# OpenBook_schematic.net
KiCad netlist of a schematic drawn in EAGLE
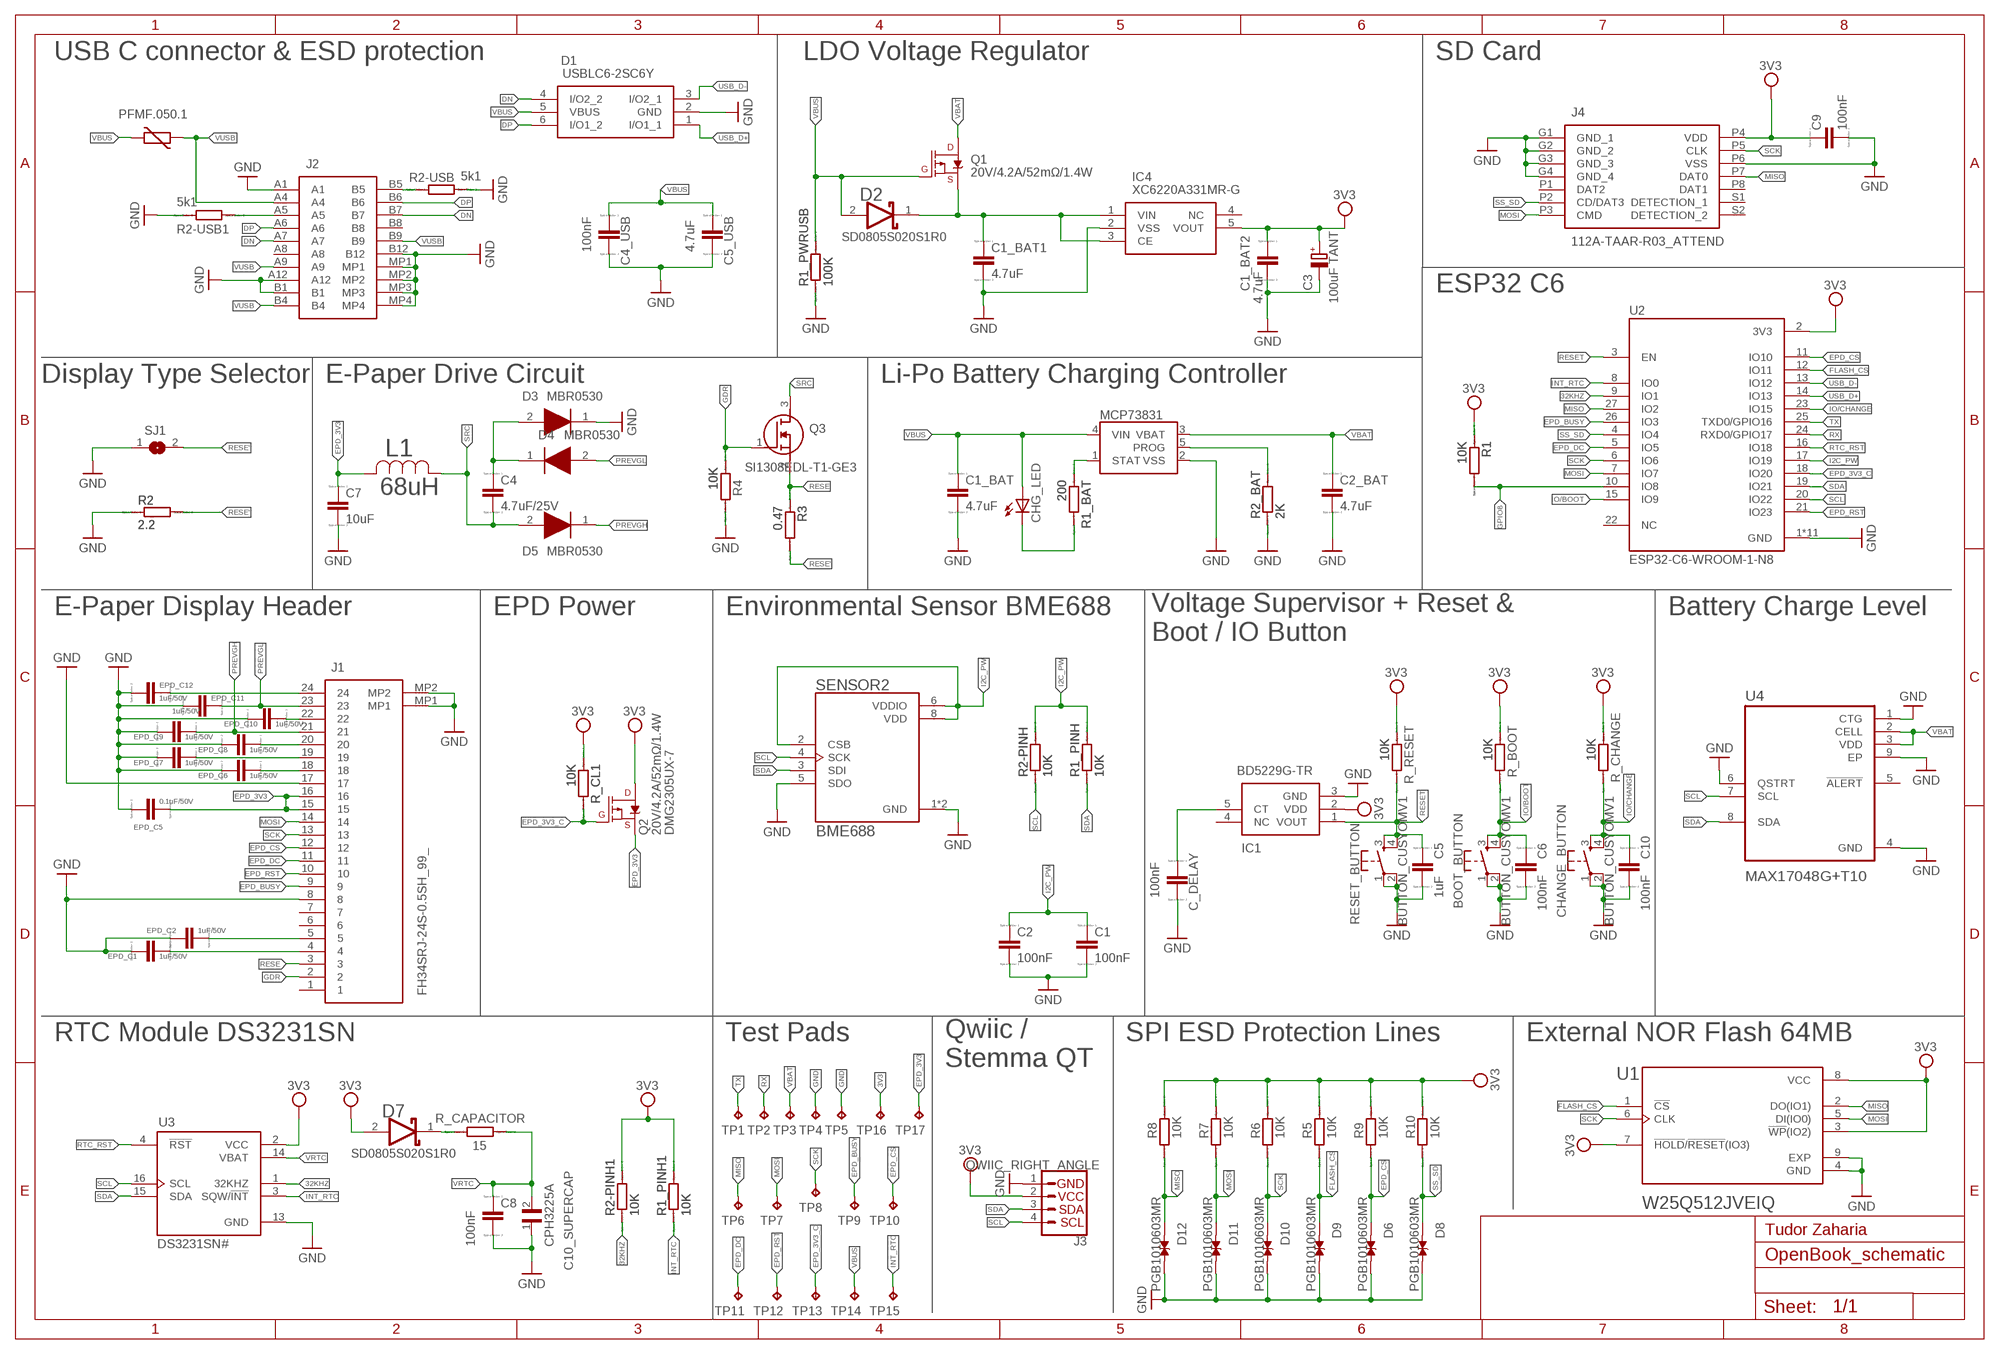
[diagram p0: schematic, sheet 1]

(export (version "E")
  (design (tool "Eeschema 10.0.6"))
  (components
    (comp (ref "BOOT_BUTTON")
      (value "BUTTON_CUSYOMV1")
      (footprint "eagle-import:MYBUTTON")
      (libsource (lib "eagle-import") (part "BUTTON_CUSYOMV1"))
    )
    (comp (ref "C1")
      (value "100nF")
      (footprint "eagle-import:EAGLE-LTSPICE_C0402")
      (libsource (lib "eagle-import") (part "EAGLE-LTSPICE_CC0402"))
    )
    (comp (ref "C1_BAT")
      (value "4.7uF")
      (footprint "eagle-import:EAGLE-LTSPICE_C0402")
      (libsource (lib "eagle-import") (part "EAGLE-LTSPICE_CC0402"))
    )
    (comp (ref "C1_BAT1")
      (value "4.7uF")
      (footprint "eagle-import:EAGLE-LTSPICE_C0402")
      (libsource (lib "eagle-import") (part "EAGLE-LTSPICE_CC0402"))
    )
    (comp (ref "C1_BAT2")
      (value "4.7uF")
      (footprint "eagle-import:EAGLE-LTSPICE_C0402")
      (libsource (lib "eagle-import") (part "EAGLE-LTSPICE_CC0402"))
    )
    (comp (ref "C2")
      (value "100nF")
      (footprint "eagle-import:EAGLE-LTSPICE_C0402")
      (libsource (lib "eagle-import") (part "EAGLE-LTSPICE_CC0402"))
    )
    (comp (ref "C2_BAT")
      (value "4.7uF")
      (footprint "eagle-import:EAGLE-LTSPICE_C0402")
      (libsource (lib "eagle-import") (part "EAGLE-LTSPICE_CC0402"))
    )
    (comp (ref "C3")
      (value "100uF TANT")
      (footprint "eagle-import:RCL_CT3528")
      (libsource (lib "eagle-import") (part "RCL_CPOL-EUCT3528"))
    )
    (comp (ref "C4")
      (value "4.7uF/25V")
      (footprint "eagle-import:EAGLE-LTSPICE_C0402")
      (libsource (lib "eagle-import") (part "EAGLE-LTSPICE_CC0402"))
    )
    (comp (ref "C4_USB")
      (value "100nF")
      (footprint "eagle-import:EAGLE-LTSPICE_C0402")
      (libsource (lib "eagle-import") (part "EAGLE-LTSPICE_CC0402"))
    )
    (comp (ref "C5")
      (value "1uF")
      (footprint "eagle-import:EAGLE-LTSPICE_C0402")
      (libsource (lib "eagle-import") (part "EAGLE-LTSPICE_CC0402"))
    )
    (comp (ref "C5_USB")
      (value "4.7uF")
      (footprint "eagle-import:EAGLE-LTSPICE_C0402")
      (libsource (lib "eagle-import") (part "EAGLE-LTSPICE_CC0402"))
    )
    (comp (ref "C6")
      (value "100nF")
      (footprint "eagle-import:EAGLE-LTSPICE_C0402")
      (libsource (lib "eagle-import") (part "EAGLE-LTSPICE_CC0402"))
    )
    (comp (ref "C7")
      (value "10uF")
      (footprint "eagle-import:EAGLE-LTSPICE_C0402")
      (libsource (lib "eagle-import") (part "EAGLE-LTSPICE_CC0402"))
    )
    (comp (ref "C8")
      (value "100nF")
      (footprint "eagle-import:EAGLE-LTSPICE_C0402")
      (libsource (lib "eagle-import") (part "EAGLE-LTSPICE_CC0402"))
    )
    (comp (ref "C9")
      (value "100nF")
      (footprint "eagle-import:EAGLE-LTSPICE_C0402")
      (libsource (lib "eagle-import") (part "EAGLE-LTSPICE_CC0402"))
    )
    (comp (ref "C10")
      (value "100nF")
      (footprint "eagle-import:EAGLE-LTSPICE_C0402")
      (libsource (lib "eagle-import") (part "EAGLE-LTSPICE_CC0402"))
    )
    (comp (ref "C10_SUPERCAP")
      (value "CPH3225A")
      (footprint "eagle-import:CAPCP3225X100N")
      (fields (field (name "MF") "Seiko Instruments"))
      (libsource (lib "eagle-import") (part "CPH3225A"))
    )
    (comp (ref "CHANGE_BUTTON")
      (value "BUTTON_CUSYOMV1")
      (footprint "eagle-import:MYBUTTON")
      (libsource (lib "eagle-import") (part "BUTTON_CUSYOMV1"))
    )
    (comp (ref "CHG_LED")
      (value "ADAFRUIT_LEDCHIP-LED0603")
      (footprint "eagle-import:ADAFRUIT_CHIP-LED0603")
      (libsource (lib "eagle-import") (part "ADAFRUIT_LEDCHIP-LED0603"))
    )
    (comp (ref "C_DELAY")
      (value "100nF")
      (footprint "eagle-import:EAGLE-LTSPICE_C0402")
      (libsource (lib "eagle-import") (part "EAGLE-LTSPICE_CC0402"))
    )
    (comp (ref "D1")
      (value "USBLC6-2SC6Y")
      (footprint "eagle-import:SOT95P280X145-6N")
      (fields (field (name "MF") "STMicroelectronics"))
      (libsource (lib "eagle-import") (part "USBLC6-2SC6Y"))
    )
    (comp (ref "D2")
      (value "ESP32_WROVER_AVX---SD0805S020S1R0_AVX_SD0805S020S1R0_0_0AVX_SD0805S020S1R0_0_0")
      (footprint "eagle-import:ESP32_WROVER_AVX---SD0805S020S1R0_AVX_SD0805S020S1R0_0")
      (fields
        (field (name "DIGIKEY_PART_NUMBER") "478-7800-1-ND")
        (field (name "MF") "AVX")
        (field (name "MOUSER_PART_NUMBER") "581-SD0805S020S1R0")
      )
      (libsource (lib "eagle-import") (part "ESP32_WROVER_AVX---SD0805S020S1R0_AVX_SD0805S020S1R0_0_0AVX_SD0805S020S1R0_0_0"))
    )
    (comp (ref "D3")
      (value "MBR0530")
      (footprint "eagle-import:SOD3716X135N")
      (fields (field (name "MF") "ON Semiconductor"))
      (libsource (lib "eagle-import") (part "MBR0530"))
    )
    (comp (ref "D4")
      (value "MBR0530")
      (footprint "eagle-import:SOD3716X135N")
      (fields (field (name "MF") "ON Semiconductor"))
      (libsource (lib "eagle-import") (part "MBR0530"))
    )
    (comp (ref "D5")
      (value "MBR0530")
      (footprint "eagle-import:SOD3716X135N")
      (fields (field (name "MF") "ON Semiconductor"))
      (libsource (lib "eagle-import") (part "MBR0530"))
    )
    (comp (ref "D6")
      (value "PGB1010603MR")
      (footprint "eagle-import:DIOC1608X36N")
      (fields (field (name "MF") "Littelfuse Inc."))
      (libsource (lib "eagle-import") (part "PGB1010603MR"))
    )
    (comp (ref "D7")
      (value "ESP32_WROVER_AVX---SD0805S020S1R0_AVX_SD0805S020S1R0_0_0AVX_SD0805S020S1R0_0_0")
      (footprint "eagle-import:ESP32_WROVER_AVX---SD0805S020S1R0_AVX_SD0805S020S1R0_0")
      (fields
        (field (name "DIGIKEY_PART_NUMBER") "478-7800-1-ND")
        (field (name "MF") "AVX")
        (field (name "MOUSER_PART_NUMBER") "581-SD0805S020S1R0")
      )
      (libsource (lib "eagle-import") (part "ESP32_WROVER_AVX---SD0805S020S1R0_AVX_SD0805S020S1R0_0_0AVX_SD0805S020S1R0_0_0"))
    )
    (comp (ref "D8")
      (value "PGB1010603MR")
      (footprint "eagle-import:DIOC1608X36N")
      (fields (field (name "MF") "Littelfuse Inc."))
      (libsource (lib "eagle-import") (part "PGB1010603MR"))
    )
    (comp (ref "D9")
      (value "PGB1010603MR")
      (footprint "eagle-import:DIOC1608X36N")
      (fields (field (name "MF") "Littelfuse Inc."))
      (libsource (lib "eagle-import") (part "PGB1010603MR"))
    )
    (comp (ref "D10")
      (value "PGB1010603MR")
      (footprint "eagle-import:DIOC1608X36N")
      (fields (field (name "MF") "Littelfuse Inc."))
      (libsource (lib "eagle-import") (part "PGB1010603MR"))
    )
    (comp (ref "D11")
      (value "PGB1010603MR")
      (footprint "eagle-import:DIOC1608X36N")
      (fields (field (name "MF") "Littelfuse Inc."))
      (libsource (lib "eagle-import") (part "PGB1010603MR"))
    )
    (comp (ref "D12")
      (value "PGB1010603MR")
      (footprint "eagle-import:DIOC1608X36N")
      (fields (field (name "MF") "Littelfuse Inc."))
      (libsource (lib "eagle-import") (part "PGB1010603MR"))
    )
    (comp (ref "EPD_C1")
      (value "1uF/50V")
      (footprint "eagle-import:EAGLE-LTSPICE_C0402")
      (libsource (lib "eagle-import") (part "EAGLE-LTSPICE_CC0402"))
    )
    (comp (ref "EPD_C2")
      (value "1uF/50V")
      (footprint "eagle-import:EAGLE-LTSPICE_C0402")
      (libsource (lib "eagle-import") (part "EAGLE-LTSPICE_CC0402"))
    )
    (comp (ref "EPD_C5")
      (value "0.1uF/50V")
      (footprint "eagle-import:EAGLE-LTSPICE_C0402")
      (libsource (lib "eagle-import") (part "EAGLE-LTSPICE_CC0402"))
    )
    (comp (ref "EPD_C6")
      (value "1uF/50V")
      (footprint "eagle-import:EAGLE-LTSPICE_C0402")
      (libsource (lib "eagle-import") (part "EAGLE-LTSPICE_CC0402"))
    )
    (comp (ref "EPD_C7")
      (value "1uF/50V")
      (footprint "eagle-import:EAGLE-LTSPICE_C0402")
      (libsource (lib "eagle-import") (part "EAGLE-LTSPICE_CC0402"))
    )
    (comp (ref "EPD_C8")
      (value "1uF/50V")
      (footprint "eagle-import:EAGLE-LTSPICE_C0402")
      (libsource (lib "eagle-import") (part "EAGLE-LTSPICE_CC0402"))
    )
    (comp (ref "EPD_C9")
      (value "1uF/50V")
      (footprint "eagle-import:EAGLE-LTSPICE_C0402")
      (libsource (lib "eagle-import") (part "EAGLE-LTSPICE_CC0402"))
    )
    (comp (ref "EPD_C10")
      (value "1uF/50V")
      (footprint "eagle-import:EAGLE-LTSPICE_C0402")
      (libsource (lib "eagle-import") (part "EAGLE-LTSPICE_CC0402"))
    )
    (comp (ref "EPD_C11")
      (value "1uF/50V")
      (footprint "eagle-import:EAGLE-LTSPICE_C0402")
      (libsource (lib "eagle-import") (part "EAGLE-LTSPICE_CC0402"))
    )
    (comp (ref "EPD_C12")
      (value "1uF/50V")
      (footprint "eagle-import:EAGLE-LTSPICE_C0402")
      (libsource (lib "eagle-import") (part "EAGLE-LTSPICE_CC0402"))
    )
    (comp (ref "IC1")
      (value "BD5229G-TR")
      (footprint "eagle-import:SOT95P280X125-5N")
      (fields (field (name "MOUSER_PART_NUMBER") "755-BD5229G-TR"))
      (libsource (lib "eagle-import") (part "BD5229G-TR"))
    )
    (comp (ref "IC4")
      (value "XC6220A331MR-G")
      (footprint "eagle-import:SOT95P280X120-5N")
      (fields (field (name "MOUSER_PART_NUMBER") "865-XC6220A331MR-G"))
      (libsource (lib "eagle-import") (part "XC6220A331MR-G"))
    )
    (comp (ref "J1")
      (value "FH34SRJ-24S-0.5SH_99_")
      (footprint "eagle-import:FH34SRJ24S05SH99")
      (fields
        (field (name "MANUFACTURER_PART_NUMBER") "FH34SRJ-24S-0.5SH(99)")
        (field (name "MOUSER_PART_NUMBER") "798-FH34SRJ24S05SH99")
      )
      (libsource (lib "eagle-import") (part "FH34SRJ-24S-0.5SH_99_"))
    )
    (comp (ref "J2")
      (value "SAMACSYS_PARTS_USB4110-GF-A")
      (footprint "eagle-import:SAMACSYS_PARTS_USB4110GFA")
      (fields
        (field (name "MANUFACTURER_PART_NUMBER") "USB4110-GF-A")
        (field (name "MOUSER_PART_NUMBER") "640-USB4110-GF-A")
      )
      (libsource (lib "eagle-import") (part "SAMACSYS_PARTS_USB4110-GF-A"))
    )
    (comp (ref "J3")
      (value "QWIIC_RIGHT_ANGLE")
      (footprint "eagle-import:JST04_1MM_RA")
      (libsource (lib "eagle-import") (part "QWIIC_CONNECTORJS-1MM"))
    )
    (comp (ref "J4")
      (value "112A-TAAR-R03_ATTEND")
      (footprint "eagle-import:112ATAARR03ATTEND")
      (fields (field (name "MANUFACTURER_PART_NUMBER") "112A-TAAR-R03 ATTEND"))
      (libsource (lib "eagle-import") (part "112A-TAAR-R03_ATTEND"))
    )
    (comp (ref "L1")
      (value "68uH")
      (footprint "eagle-import:IND_4828-WE-TPC_WRE")
      (fields
        (field (name "MANUFACTURER_PART_NUMBER") "744043680")
        (field (name "COPYRIGHT") "Copyright (C) 2024 Ultra Librarian. All rights reserved.")
      )
      (libsource (lib "eagle-import") (part "744043680IND_4828-WE-TPC_WRE"))
    )
    (comp (ref "MCP73831")
      (value "ESP32_WROVER_SPARKFUN-IC-POWER_MCP73831")
      (footprint "eagle-import:ESP32_WROVER_SPARKFUN-IC-POWER_SOT23-5")
      (libsource (lib "eagle-import") (part "ESP32_WROVER_SPARKFUN-IC-POWER_MCP73831"))
    )
    (comp (ref "PFMF.050.1")
      (value "ESP32C6_VARISTORCN1812")
      (footprint "eagle-import:ESP32C6_VARISTOR_CT_CN1812")
      (libsource (lib "eagle-import") (part "ESP32C6_VARISTORCN1812"))
    )
    (comp (ref "Q1")
      (value "20V/4.2A/52mΩ/1.4W")
      (footprint "eagle-import:ESP32_WROVER_SPARKFUN-DISCRETESEMI_SOT23-3")
      (libsource (lib "eagle-import") (part "ESP32_WROVER_SPARKFUN-DISCRETESEMI_MOSFET_PCH-DMG2305UX-7"))
    )
    (comp (ref "Q2")
      (value "20V/4.2A/52mΩ/1.4W")
      (footprint "eagle-import:ESP32_WROVER_SPARKFUN-DISCRETESEMI_SOT23-3")
      (libsource (lib "eagle-import") (part "ESP32_WROVER_SPARKFUN-DISCRETESEMI_MOSFET_PCH-DMG2305UX-7"))
    )
    (comp (ref "Q3")
      (value "SI1308EDL-T1-GE3")
      (footprint "eagle-import:SOT65P210X110-3N")
      (fields (field (name "MF") "Vishay Siliconix"))
      (libsource (lib "eagle-import") (part "SI1308EDL-T1-GE3"))
    )
    (comp (ref "R1")
      (value "10K")
      (footprint "eagle-import:ESP32_WROVER_EAGLE-LTSPICE_R0402")
      (libsource (lib "eagle-import") (part "ESP32_WROVER_EAGLE-LTSPICE_RR0402"))
    )
    (comp (ref "R1_BAT")
      (value "200")
      (footprint "eagle-import:ESP32_WROVER_EAGLE-LTSPICE_R0402")
      (libsource (lib "eagle-import") (part "ESP32_WROVER_EAGLE-LTSPICE_RR0402"))
    )
    (comp (ref "R1_PINH")
      (value "10K")
      (footprint "eagle-import:ESP32_WROVER_EAGLE-LTSPICE_R0402")
      (libsource (lib "eagle-import") (part "ESP32_WROVER_EAGLE-LTSPICE_RR0402"))
    )
    (comp (ref "R1_PINH1")
      (value "10K")
      (footprint "eagle-import:ESP32_WROVER_EAGLE-LTSPICE_R0402")
      (libsource (lib "eagle-import") (part "ESP32_WROVER_EAGLE-LTSPICE_RR0402"))
    )
    (comp (ref "R1_PWRUSB")
      (value "100K")
      (footprint "eagle-import:ESP32_WROVER_EAGLE-LTSPICE_R0402")
      (libsource (lib "eagle-import") (part "ESP32_WROVER_EAGLE-LTSPICE_RR0402"))
    )
    (comp (ref "R2")
      (value "2.2")
      (footprint "eagle-import:ESP32_WROVER_EAGLE-LTSPICE_R0402")
      (libsource (lib "eagle-import") (part "ESP32_WROVER_EAGLE-LTSPICE_RR0402"))
    )
    (comp (ref "R2-PINH")
      (value "10K")
      (footprint "eagle-import:ESP32_WROVER_EAGLE-LTSPICE_R0402")
      (libsource (lib "eagle-import") (part "ESP32_WROVER_EAGLE-LTSPICE_RR0402"))
    )
    (comp (ref "R2-PINH1")
      (value "10K")
      (footprint "eagle-import:ESP32_WROVER_EAGLE-LTSPICE_R0402")
      (libsource (lib "eagle-import") (part "ESP32_WROVER_EAGLE-LTSPICE_RR0402"))
    )
    (comp (ref "R2-USB")
      (value "5k1")
      (footprint "eagle-import:ESP32_WROVER_EAGLE-LTSPICE_R0402")
      (libsource (lib "eagle-import") (part "ESP32_WROVER_EAGLE-LTSPICE_RR0402"))
    )
    (comp (ref "R2-USB1")
      (value "5k1")
      (footprint "eagle-import:ESP32_WROVER_EAGLE-LTSPICE_R0402")
      (libsource (lib "eagle-import") (part "ESP32_WROVER_EAGLE-LTSPICE_RR0402"))
    )
    (comp (ref "R2_BAT")
      (value "2K")
      (footprint "eagle-import:ESP32_WROVER_EAGLE-LTSPICE_R0402")
      (libsource (lib "eagle-import") (part "ESP32_WROVER_EAGLE-LTSPICE_RR0402"))
    )
    (comp (ref "R3")
      (value "0.47")
      (footprint "eagle-import:ESP32_WROVER_EAGLE-LTSPICE_R0402")
      (libsource (lib "eagle-import") (part "ESP32_WROVER_EAGLE-LTSPICE_RR0402"))
    )
    (comp (ref "R4")
      (value "10K")
      (footprint "eagle-import:ESP32_WROVER_EAGLE-LTSPICE_R0402")
      (libsource (lib "eagle-import") (part "ESP32_WROVER_EAGLE-LTSPICE_RR0402"))
    )
    (comp (ref "R5")
      (value "10K")
      (footprint "eagle-import:ESP32_WROVER_EAGLE-LTSPICE_R0402")
      (libsource (lib "eagle-import") (part "ESP32_WROVER_EAGLE-LTSPICE_RR0402"))
    )
    (comp (ref "R6")
      (value "10K")
      (footprint "eagle-import:ESP32_WROVER_EAGLE-LTSPICE_R0402")
      (libsource (lib "eagle-import") (part "ESP32_WROVER_EAGLE-LTSPICE_RR0402"))
    )
    (comp (ref "R7")
      (value "10K")
      (footprint "eagle-import:ESP32_WROVER_EAGLE-LTSPICE_R0402")
      (libsource (lib "eagle-import") (part "ESP32_WROVER_EAGLE-LTSPICE_RR0402"))
    )
    (comp (ref "R8")
      (value "10K")
      (footprint "eagle-import:ESP32_WROVER_EAGLE-LTSPICE_R0402")
      (libsource (lib "eagle-import") (part "ESP32_WROVER_EAGLE-LTSPICE_RR0402"))
    )
    (comp (ref "R9")
      (value "10K")
      (footprint "eagle-import:ESP32_WROVER_EAGLE-LTSPICE_R0402")
      (libsource (lib "eagle-import") (part "ESP32_WROVER_EAGLE-LTSPICE_RR0402"))
    )
    (comp (ref "R10")
      (value "10K")
      (footprint "eagle-import:ESP32_WROVER_EAGLE-LTSPICE_R0402")
      (libsource (lib "eagle-import") (part "ESP32_WROVER_EAGLE-LTSPICE_RR0402"))
    )
    (comp (ref "RESET_BUTTON")
      (value "BUTTON_CUSYOMV1")
      (footprint "eagle-import:MYBUTTON")
      (libsource (lib "eagle-import") (part "BUTTON_CUSYOMV1"))
    )
    (comp (ref "R_BOOT")
      (value "10K")
      (footprint "eagle-import:ESP32_WROVER_EAGLE-LTSPICE_R0402")
      (libsource (lib "eagle-import") (part "ESP32_WROVER_EAGLE-LTSPICE_RR0402"))
    )
    (comp (ref "R_CAPACITOR")
      (value "15")
      (footprint "eagle-import:ESP32_WROVER_EAGLE-LTSPICE_R0402")
      (libsource (lib "eagle-import") (part "ESP32_WROVER_EAGLE-LTSPICE_RR0402"))
    )
    (comp (ref "R_CHANGE")
      (value "10K")
      (footprint "eagle-import:ESP32_WROVER_EAGLE-LTSPICE_R0402")
      (libsource (lib "eagle-import") (part "ESP32_WROVER_EAGLE-LTSPICE_RR0402"))
    )
    (comp (ref "R_CL1")
      (value "10K")
      (footprint "eagle-import:ESP32_WROVER_EAGLE-LTSPICE_R0402")
      (libsource (lib "eagle-import") (part "ESP32_WROVER_EAGLE-LTSPICE_RR0402"))
    )
    (comp (ref "R_RESET")
      (value "10K")
      (footprint "eagle-import:ESP32_WROVER_EAGLE-LTSPICE_R0402")
      (libsource (lib "eagle-import") (part "ESP32_WROVER_EAGLE-LTSPICE_RR0402"))
    )
    (comp (ref "SENSOR2")
      (value "BME688")
      (footprint "eagle-import:ESP32_WROVER_BME680_PSON80P300X300X100-8N")
      (fields (field (name "MF") "Bosch Sensortec") (field (name "MP") "BME680"))
      (libsource (lib "eagle-import") (part "ESP32_WROVER_BME680_BME680"))
    )
    (comp (ref "SJ1") (value "SJ") (footprint "eagle-import:SJ") (libsource (lib "eagle-import") (part "SJ")))
    (comp (ref "TP1")
      (value "TX")
      (footprint "eagle-import:TP20R")
      (libsource (lib "eagle-import") (part "TPTP20R"))
    )
    (comp (ref "TP2")
      (value "RX")
      (footprint "eagle-import:TP20R")
      (libsource (lib "eagle-import") (part "TPTP20R"))
    )
    (comp (ref "TP3")
      (value "VBAT")
      (footprint "eagle-import:TP20R")
      (libsource (lib "eagle-import") (part "TPTP20R"))
    )
    (comp (ref "TP4")
      (value "GND")
      (footprint "eagle-import:TP20R")
      (libsource (lib "eagle-import") (part "TPTP20R"))
    )
    (comp (ref "TP5")
      (value "GND")
      (footprint "eagle-import:TP20R")
      (libsource (lib "eagle-import") (part "TPTP20R"))
    )
    (comp (ref "TP6")
      (value "MISO")
      (footprint "eagle-import:TP20R")
      (libsource (lib "eagle-import") (part "TPTP20R"))
    )
    (comp (ref "TP7")
      (value "MOSI")
      (footprint "eagle-import:TP20R")
      (libsource (lib "eagle-import") (part "TPTP20R"))
    )
    (comp (ref "TP8")
      (value "SCK")
      (footprint "eagle-import:TP20R")
      (libsource (lib "eagle-import") (part "TPTP20R"))
    )
    (comp (ref "TP9")
      (value "EPD_BUSY")
      (footprint "eagle-import:TP20R")
      (libsource (lib "eagle-import") (part "TPTP20R"))
    )
    (comp (ref "TP10")
      (value "EPD_CS")
      (footprint "eagle-import:TP20R")
      (libsource (lib "eagle-import") (part "TPTP20R"))
    )
    (comp (ref "TP11")
      (value "EPD_DC")
      (footprint "eagle-import:TP20R")
      (libsource (lib "eagle-import") (part "TPTP20R"))
    )
    (comp (ref "TP12")
      (value "EPD_RST")
      (footprint "eagle-import:TP20R")
      (libsource (lib "eagle-import") (part "TPTP20R"))
    )
    (comp (ref "TP13")
      (value "EPD_3V3_C")
      (footprint "eagle-import:TP20R")
      (libsource (lib "eagle-import") (part "TPTP20R"))
    )
    (comp (ref "TP14")
      (value "VBUS")
      (footprint "eagle-import:TP20R")
      (libsource (lib "eagle-import") (part "TPTP20R"))
    )
    (comp (ref "TP15")
      (value "INT_RTC")
      (footprint "eagle-import:TP20R")
      (libsource (lib "eagle-import") (part "TPTP20R"))
    )
    (comp (ref "TP16")
      (value "3V3")
      (footprint "eagle-import:TP20R")
      (libsource (lib "eagle-import") (part "TPTP20R"))
    )
    (comp (ref "TP17")
      (value "EPD_3V3")
      (footprint "eagle-import:TP20R")
      (libsource (lib "eagle-import") (part "TPTP20R"))
    )
    (comp (ref "U1")
      (value "W25Q512JVEIQ")
      (footprint "eagle-import:SON127P600X800X80-9N")
      (fields (field (name "MF") "Winbond Electronics"))
      (libsource (lib "eagle-import") (part "W25Q512JVEIQ"))
    )
    (comp (ref "U2")
      (value "ESP32-C6-WROOM-1-N8")
      (footprint "eagle-import:XCVR_ESP32-C6-WROOM-1-N8")
      (fields (field (name "MF") "Espressif Systems"))
      (libsource (lib "eagle-import") (part "ESP32-C6-WROOM-1-N8"))
    )
    (comp (ref "U3")
      (value "DS3231SN#")
      (footprint "eagle-import:SOIC127P1032X265-16N")
      (fields (field (name "MF") "Analog Devices"))
      (libsource (lib "eagle-import") (part "DS3231SN#"))
    )
    (comp (ref "U4")
      (value "MAX17048G+T10")
      (footprint "eagle-import:SON50P200X200X80-9N")
      (fields (field (name "MF") "Analog Devices"))
      (libsource (lib "eagle-import") (part "MAX17048G+T10"))
    )
  )
  (nets
    (net (code "1") (name "3V3") (class "Default")
      (node (ref "C1_BAT2") (pin "1") (pinfunction "1_1") (pintype "passive"))
      (node (ref "C3") (pin "+") (pinfunction "+_+") (pintype "passive"))
      (node (ref "C9") (pin "1") (pinfunction "1_1") (pintype "passive"))
      (node (ref "D7") (pin "2") (pinfunction "ANODE_2") (pintype "bidirectional"))
      (node (ref "IC1") (pin "2") (pinfunction "VDD_2") (pintype "bidirectional"))
      (node (ref "IC4") (pin "5") (pinfunction "VOUT_5") (pintype "bidirectional"))
      (node (ref "J3") (pin "2") (pinfunction "2_2") (pintype "power_in"))
      (node (ref "J4") (pin "P4") (pinfunction "VDD_P4") (pintype "bidirectional"))
      (node (ref "Q2") (pin "3") (pinfunction "D_3") (pintype "bidirectional"))
      (node (ref "R1") (pin "1") (pinfunction "1_1") (pintype "passive"))
      (node (ref "R10") (pin "2") (pinfunction "2_2") (pintype "passive"))
      (node (ref "R1_PINH1") (pin "2") (pinfunction "2_2") (pintype "passive"))
      (node (ref "R2-PINH1") (pin "2") (pinfunction "2_2") (pintype "passive"))
      (node (ref "R5") (pin "2") (pinfunction "2_2") (pintype "passive"))
      (node (ref "R6") (pin "2") (pinfunction "2_2") (pintype "passive"))
      (node (ref "R7") (pin "2") (pinfunction "2_2") (pintype "passive"))
      (node (ref "R8") (pin "2") (pinfunction "2_2") (pintype "passive"))
      (node (ref "R9") (pin "2") (pinfunction "2_2") (pintype "passive"))
      (node (ref "R_BOOT") (pin "1") (pinfunction "1_1") (pintype "passive"))
      (node (ref "R_CHANGE") (pin "1") (pinfunction "1_1") (pintype "passive"))
      (node (ref "R_CL1") (pin "1") (pinfunction "1_1") (pintype "passive"))
      (node (ref "R_RESET") (pin "1") (pinfunction "1_1") (pintype "passive"))
      (node (ref "TP16") (pin "TP") (pinfunction "TP_TP") (pintype "input"))
      (node (ref "U1") (pin "3") (pinfunction "~{WP}(IO2)_3") (pintype "bidirectional"))
      (node (ref "U1") (pin "7") (pinfunction "~{HOLD}/~{RESET}(IO3)_7") (pintype "bidirectional"))
      (node (ref "U1") (pin "8") (pinfunction "VCC_8") (pintype "power_in"))
      (node (ref "U2") (pin "2") (pinfunction "3V3_2") (pintype "power_in"))
      (node (ref "U3") (pin "2") (pinfunction "VCC_2") (pintype "power_in"))
    )
    (net (code "2") (name "32KHZ") (class "Default")
      (node (ref "R2-PINH1") (pin "1") (pinfunction "1_1") (pintype "passive"))
      (node (ref "U2") (pin "9") (pinfunction "IO1_9") (pintype "bidirectional"))
      (node (ref "U3") (pin "1") (pinfunction "32KHZ_1") (pintype "output"))
    )
    (net (code "3") (name "DN") (class "Default")
      (node (ref "D1") (pin "4") (pinfunction "I/O2_2_4") (pintype "bidirectional"))
      (node (ref "J2") (pin "A7") (pinfunction "A7_A7") (pintype "bidirectional"))
      (node (ref "J2") (pin "B7") (pinfunction "B7_B7") (pintype "bidirectional"))
    )
    (net (code "4") (name "DP") (class "Default")
      (node (ref "D1") (pin "6") (pinfunction "I/O1_2_6") (pintype "bidirectional"))
      (node (ref "J2") (pin "A6") (pinfunction "A6_A6") (pintype "bidirectional"))
      (node (ref "J2") (pin "B6") (pinfunction "B6_B6") (pintype "bidirectional"))
    )
    (net (code "5") (name "EPD_3V3") (class "Default")
      (node (ref "C7") (pin "1") (pinfunction "1_1") (pintype "passive"))
      (node (ref "EPD_C5") (pin "1") (pinfunction "1_1") (pintype "passive"))
      (node (ref "J1") (pin "15") (pinfunction "15_15") (pintype "bidirectional"))
      (node (ref "J1") (pin "16") (pinfunction "16_16") (pintype "bidirectional"))
      (node (ref "L1") (pin "2") (pinfunction "2_2") (pintype "passive"))
      (node (ref "Q2") (pin "2") (pinfunction "S_2") (pintype "bidirectional"))
      (node (ref "TP17") (pin "TP") (pinfunction "TP_TP") (pintype "input"))
    )
    (net (code "6") (name "EPD_3V3_C") (class "Default")
      (node (ref "Q2") (pin "1") (pinfunction "G_1") (pintype "bidirectional"))
      (node (ref "R_CL1") (pin "2") (pinfunction "2_2") (pintype "passive"))
      (node (ref "TP13") (pin "TP") (pinfunction "TP_TP") (pintype "input"))
      (node (ref "U2") (pin "18") (pinfunction "IO20_18") (pintype "bidirectional"))
    )
    (net (code "7") (name "EPD_BUSY") (class "Default")
      (node (ref "J1") (pin "9") (pinfunction "9_9") (pintype "bidirectional"))
      (node (ref "TP9") (pin "TP") (pinfunction "TP_TP") (pintype "input"))
      (node (ref "U2") (pin "26") (pinfunction "IO3_26") (pintype "bidirectional"))
    )
    (net (code "8") (name "EPD_CS") (class "Default")
      (node (ref "D6") (pin "1") (pinfunction "1_1") (pintype "passive"))
      (node (ref "J1") (pin "12") (pinfunction "12_12") (pintype "bidirectional"))
      (node (ref "R9") (pin "1") (pinfunction "1_1") (pintype "passive"))
      (node (ref "TP10") (pin "TP") (pinfunction "TP_TP") (pintype "input"))
      (node (ref "U2") (pin "11") (pinfunction "IO10_11") (pintype "bidirectional"))
    )
    (net (code "9") (name "EPD_DC") (class "Default")
      (node (ref "J1") (pin "11") (pinfunction "11_11") (pintype "bidirectional"))
      (node (ref "TP11") (pin "TP") (pinfunction "TP_TP") (pintype "input"))
      (node (ref "U2") (pin "5") (pinfunction "IO5_5") (pintype "bidirectional"))
    )
    (net (code "10") (name "EPD_RST") (class "Default")
      (node (ref "J1") (pin "10") (pinfunction "10_10") (pintype "bidirectional"))
      (node (ref "TP12") (pin "TP") (pinfunction "TP_TP") (pintype "input"))
      (node (ref "U2") (pin "21") (pinfunction "IO23_21") (pintype "bidirectional"))
    )
    (net (code "11") (name "FLASH_CS") (class "Default")
      (node (ref "D9") (pin "1") (pinfunction "1_1") (pintype "passive"))
      (node (ref "R5") (pin "1") (pinfunction "1_1") (pintype "passive"))
      (node (ref "U1") (pin "1") (pinfunction "~{CS}_1") (pintype "input"))
      (node (ref "U2") (pin "12") (pinfunction "IO11_12") (pintype "bidirectional"))
    )
    (net (code "12") (name "GDR") (class "Default")
      (node (ref "J1") (pin "2") (pinfunction "2_2") (pintype "bidirectional"))
      (node (ref "Q3") (pin "1") (pinfunction "G_1") (pintype "bidirectional"))
      (node (ref "R4") (pin "1") (pinfunction "1_1") (pintype "passive"))
    )
    (net (code "13") (name "GND") (class "Default")
      (node (ref "BOOT_BUTTON") (pin "1") (pinfunction "1_1") (pintype "passive"))
      (node (ref "BOOT_BUTTON") (pin "2") (pinfunction "2_2") (pintype "passive"))
      (node (ref "C1") (pin "2") (pinfunction "2_2") (pintype "passive"))
      (node (ref "C10") (pin "2") (pinfunction "2_2") (pintype "passive"))
      (node (ref "C10_SUPERCAP") (pin "1") (pinfunction "1_1") (pintype "passive"))
      (node (ref "C1_BAT") (pin "2") (pinfunction "2_2") (pintype "passive"))
      (node (ref "C1_BAT1") (pin "2") (pinfunction "2_2") (pintype "passive"))
      (node (ref "C1_BAT2") (pin "2") (pinfunction "2_2") (pintype "passive"))
      (node (ref "C2") (pin "2") (pinfunction "2_2") (pintype "passive"))
      (node (ref "C2_BAT") (pin "2") (pinfunction "2_2") (pintype "passive"))
      (node (ref "C3") (pin "-") (pinfunction "-_-") (pintype "passive"))
      (node (ref "C4_USB") (pin "2") (pinfunction "2_2") (pintype "passive"))
      (node (ref "C5") (pin "2") (pinfunction "2_2") (pintype "passive"))
      (node (ref "C5_USB") (pin "2") (pinfunction "2_2") (pintype "passive"))
      (node (ref "C6") (pin "2") (pinfunction "2_2") (pintype "passive"))
      (node (ref "C7") (pin "2") (pinfunction "2_2") (pintype "passive"))
      (node (ref "C8") (pin "2") (pinfunction "2_2") (pintype "passive"))
      (node (ref "C9") (pin "2") (pinfunction "2_2") (pintype "passive"))
      (node (ref "CHANGE_BUTTON") (pin "1") (pinfunction "1_1") (pintype "passive"))
      (node (ref "CHANGE_BUTTON") (pin "2") (pinfunction "2_2") (pintype "passive"))
      (node (ref "C_DELAY") (pin "2") (pinfunction "2_2") (pintype "passive"))
      (node (ref "D1") (pin "2") (pinfunction "GND_2") (pintype "bidirectional"))
      (node (ref "D10") (pin "2") (pinfunction "2_2") (pintype "passive"))
      (node (ref "D11") (pin "2") (pinfunction "2_2") (pintype "passive"))
      (node (ref "D12") (pin "2") (pinfunction "2_2") (pintype "passive"))
      (node (ref "D3") (pin "1") (pinfunction "K_1") (pintype "bidirectional"))
      (node (ref "D6") (pin "2") (pinfunction "2_2") (pintype "passive"))
      (node (ref "D8") (pin "2") (pinfunction "2_2") (pintype "passive"))
      (node (ref "D9") (pin "2") (pinfunction "2_2") (pintype "passive"))
      (node (ref "EPD_C1") (pin "2") (pinfunction "2_2") (pintype "passive"))
      (node (ref "EPD_C10") (pin "2") (pinfunction "2_2") (pintype "passive"))
      (node (ref "EPD_C11") (pin "2") (pinfunction "2_2") (pintype "passive"))
      (node (ref "EPD_C12") (pin "2") (pinfunction "2_2") (pintype "passive"))
      (node (ref "EPD_C2") (pin "2") (pinfunction "2_2") (pintype "passive"))
      (node (ref "EPD_C5") (pin "2") (pinfunction "2_2") (pintype "passive"))
      (node (ref "EPD_C6") (pin "2") (pinfunction "2_2") (pintype "passive"))
      (node (ref "EPD_C7") (pin "2") (pinfunction "2_2") (pintype "passive"))
      (node (ref "EPD_C8") (pin "2") (pinfunction "2_2") (pintype "passive"))
      (node (ref "EPD_C9") (pin "2") (pinfunction "2_2") (pintype "passive"))
      (node (ref "IC1") (pin "3") (pinfunction "GND_3") (pintype "bidirectional"))
      (node (ref "IC4") (pin "2") (pinfunction "VSS_2") (pintype "bidirectional"))
      (node (ref "J1") (pin "17") (pinfunction "17_17") (pintype "bidirectional"))
      (node (ref "J1") (pin "8") (pinfunction "8_8") (pintype "bidirectional"))
      (node (ref "J1") (pin "MP1") (pinfunction "MP1_MP1") (pintype "bidirectional"))
      (node (ref "J1") (pin "MP2") (pinfunction "MP2_MP2") (pintype "bidirectional"))
      (node (ref "J2") (pin "A1") (pinfunction "A1_A1") (pintype "bidirectional"))
      (node (ref "J2") (pin "A12") (pinfunction "A12_A12") (pintype "bidirectional"))
      (node (ref "J2") (pin "B1") (pinfunction "B1_B1") (pintype "bidirectional"))
      (node (ref "J2") (pin "B12") (pinfunction "B12_B12") (pintype "bidirectional"))
      (node (ref "J2") (pin "MP1") (pinfunction "MP1_MP1") (pintype "bidirectional"))
      (node (ref "J2") (pin "MP2") (pinfunction "MP2_MP2") (pintype "bidirectional"))
      (node (ref "J2") (pin "MP3") (pinfunction "MP3_MP3") (pintype "bidirectional"))
      (node (ref "J2") (pin "MP4") (pinfunction "MP4_MP4") (pintype "bidirectional"))
      (node (ref "J3") (pin "1") (pinfunction "1_1") (pintype "power_in"))
      (node (ref "J4") (pin "G1") (pinfunction "GND_1_G1") (pintype "bidirectional"))
      (node (ref "J4") (pin "G2") (pinfunction "GND_2_G2") (pintype "bidirectional"))
      (node (ref "J4") (pin "G3") (pinfunction "GND_3_G3") (pintype "bidirectional"))
      (node (ref "J4") (pin "G4") (pinfunction "GND_4_G4") (pintype "bidirectional"))
      (node (ref "J4") (pin "P6") (pinfunction "VSS_P6") (pintype "bidirectional"))
      (node (ref "MCP73831") (pin "2") (pinfunction "VSS_2") (pintype "power_in"))
      (node (ref "R1_PWRUSB") (pin "1") (pinfunction "1_1") (pintype "passive"))
      (node (ref "R2") (pin "1") (pinfunction "1_1") (pintype "passive"))
      (node (ref "R2-USB") (pin "2") (pinfunction "2_2") (pintype "passive"))
      (node (ref "R2-USB1") (pin "1") (pinfunction "1_1") (pintype "passive"))
      (node (ref "R2_BAT") (pin "1") (pinfunction "1_1") (pintype "passive"))
      (node (ref "R4") (pin "2") (pinfunction "2_2") (pintype "passive"))
      (node (ref "RESET_BUTTON") (pin "1") (pinfunction "1_1") (pintype "passive"))
      (node (ref "RESET_BUTTON") (pin "2") (pinfunction "2_2") (pintype "passive"))
      (node (ref "SENSOR2") (pin "1") (pinfunction "GND_1") (pintype "power_in"))
      (node (ref "SENSOR2") (pin "5") (pinfunction "SDO_5") (pintype "bidirectional"))
      (node (ref "SENSOR2") (pin "7") (pinfunction "GND_7") (pintype "power_in"))
      (node (ref "SJ1") (pin "1") (pinfunction "1_1") (pintype "passive"))
      (node (ref "TP4") (pin "TP") (pinfunction "TP_TP") (pintype "input"))
      (node (ref "TP5") (pin "TP") (pinfunction "TP_TP") (pintype "input"))
      (node (ref "U1") (pin "4") (pinfunction "GND_4") (pintype "power_in"))
      (node (ref "U1") (pin "9") (pinfunction "EXP_9") (pintype "passive"))
      (node (ref "U2") (pin "1") (pinfunction "GND_1") (pintype "power_in"))
      (node (ref "U2") (pin "28") (pinfunction "GND_28") (pintype "power_in"))
      (node (ref "U2") (pin "29_1") (pinfunction "GND_29_1") (pintype "power_in"))
      (node (ref "U2") (pin "29_2") (pinfunction "GND_29_2") (pintype "power_in"))
      (node (ref "U2") (pin "29_3") (pinfunction "GND_29_3") (pintype "power_in"))
      (node (ref "U2") (pin "29_4") (pinfunction "GND_29_4") (pintype "power_in"))
      (node (ref "U2") (pin "29_5") (pinfunction "GND_29_5") (pintype "power_in"))
      (node (ref "U2") (pin "29_6") (pinfunction "GND_29_6") (pintype "power_in"))
      (node (ref "U2") (pin "29_7") (pinfunction "GND_29_7") (pintype "power_in"))
      (node (ref "U2") (pin "29_8") (pinfunction "GND_29_8") (pintype "power_in"))
      (node (ref "U2") (pin "29_9") (pinfunction "GND_29_9") (pintype "power_in"))
      (node (ref "U3") (pin "13") (pinfunction "GND_13") (pintype "power_in"))
      (node (ref "U4") (pin "1") (pinfunction "CTG_1") (pintype "power_in"))
      (node (ref "U4") (pin "4") (pinfunction "GND_4") (pintype "power_in"))
      (node (ref "U4") (pin "6") (pinfunction "QSTRT_6") (pintype "input"))
      (node (ref "U4") (pin "9") (pinfunction "EP_9") (pintype "power_in"))
    )
    (net (code "14") (name "GPIO8") (class "Default")
      (node (ref "R1") (pin "2") (pinfunction "2_2") (pintype "passive"))
      (node (ref "U2") (pin "10") (pinfunction "IO8_10") (pintype "bidirectional"))
    )
    (net (code "15") (name "I2C_PW") (class "Default")
      (node (ref "C1") (pin "1") (pinfunction "1_1") (pintype "passive"))
      (node (ref "C2") (pin "1") (pinfunction "1_1") (pintype "passive"))
      (node (ref "R1_PINH") (pin "2") (pinfunction "2_2") (pintype "passive"))
      (node (ref "R2-PINH") (pin "2") (pinfunction "2_2") (pintype "passive"))
      (node (ref "SENSOR2") (pin "2") (pinfunction "CSB_2") (pintype "input"))
      (node (ref "SENSOR2") (pin "6") (pinfunction "VDDIO_6") (pintype "power_in"))
      (node (ref "SENSOR2") (pin "8") (pinfunction "VDD_8") (pintype "power_in"))
      (node (ref "U2") (pin "17") (pinfunction "IO19_17") (pintype "bidirectional"))
    )
    (net (code "16") (name "INT_RTC") (class "Default")
      (node (ref "R1_PINH1") (pin "1") (pinfunction "1_1") (pintype "passive"))
      (node (ref "TP15") (pin "TP") (pinfunction "TP_TP") (pintype "input"))
      (node (ref "U2") (pin "8") (pinfunction "IO0_8") (pintype "bidirectional"))
      (node (ref "U3") (pin "3") (pinfunction "SQW/~{INT}_3") (pintype "output"))
    )
    (net (code "17") (name "IO{slash}BOOT") (class "Default")
      (node (ref "BOOT_BUTTON") (pin "3") (pinfunction "3_3") (pintype "passive"))
      (node (ref "BOOT_BUTTON") (pin "4") (pinfunction "4_4") (pintype "passive"))
      (node (ref "C6") (pin "1") (pinfunction "1_1") (pintype "passive"))
      (node (ref "R_BOOT") (pin "2") (pinfunction "2_2") (pintype "passive"))
      (node (ref "U2") (pin "15") (pinfunction "IO9_15") (pintype "bidirectional"))
    )
    (net (code "18") (name "IO{slash}CHANGE") (class "Default")
      (node (ref "C10") (pin "1") (pinfunction "1_1") (pintype "passive"))
      (node (ref "CHANGE_BUTTON") (pin "3") (pinfunction "3_3") (pintype "passive"))
      (node (ref "CHANGE_BUTTON") (pin "4") (pinfunction "4_4") (pintype "passive"))
      (node (ref "R_CHANGE") (pin "2") (pinfunction "2_2") (pintype "passive"))
      (node (ref "U2") (pin "23") (pinfunction "IO15_23") (pintype "bidirectional"))
    )
    (net (code "19") (name "MISO") (class "Default")
      (node (ref "D12") (pin "1") (pinfunction "1_1") (pintype "passive"))
      (node (ref "J4") (pin "P7") (pinfunction "DAT0_P7") (pintype "bidirectional"))
      (node (ref "R8") (pin "1") (pinfunction "1_1") (pintype "passive"))
      (node (ref "TP6") (pin "TP") (pinfunction "TP_TP") (pintype "input"))
      (node (ref "U1") (pin "2") (pinfunction "DO(IO1)_2") (pintype "bidirectional"))
      (node (ref "U2") (pin "27") (pinfunction "IO2_27") (pintype "bidirectional"))
    )
    (net (code "20") (name "MOSI") (class "Default")
      (node (ref "D11") (pin "1") (pinfunction "1_1") (pintype "passive"))
      (node (ref "J1") (pin "14") (pinfunction "14_14") (pintype "bidirectional"))
      (node (ref "J4") (pin "P3") (pinfunction "CMD_P3") (pintype "bidirectional"))
      (node (ref "R7") (pin "1") (pinfunction "1_1") (pintype "passive"))
      (node (ref "TP7") (pin "TP") (pinfunction "TP_TP") (pintype "input"))
      (node (ref "U1") (pin "5") (pinfunction "DI(IO0)_5") (pintype "bidirectional"))
      (node (ref "U2") (pin "7") (pinfunction "IO7_7") (pintype "bidirectional"))
    )
    (net (code "21") (name "Net-(CHG_LED-PadC)") (class "Default")
      (node (ref "CHG_LED") (pin "C") (pinfunction "C_C") (pintype "passive"))
      (node (ref "R1_BAT") (pin "2") (pinfunction "2_2") (pintype "passive"))
    )
    (net (code "22") (name "Net-(D2-CATHODE)") (class "Default")
      (node (ref "C1_BAT1") (pin "1") (pinfunction "1_1") (pintype "passive"))
      (node (ref "D2") (pin "1") (pinfunction "CATHODE_1") (pintype "bidirectional"))
      (node (ref "IC4") (pin "1") (pinfunction "VIN_1") (pintype "bidirectional"))
      (node (ref "IC4") (pin "3") (pinfunction "CE_3") (pintype "bidirectional"))
      (node (ref "Q1") (pin "2") (pinfunction "S_2") (pintype "bidirectional"))
    )
    (net (code "23") (name "Net-(D3-A)") (class "Default")
      (node (ref "C4") (pin "1") (pinfunction "1_1") (pintype "passive"))
      (node (ref "D3") (pin "2") (pinfunction "A_2") (pintype "bidirectional"))
      (node (ref "D4") (pin "1") (pinfunction "K_1") (pintype "bidirectional"))
    )
    (net (code "24") (name "Net-(D7-CATHODE)") (class "Default")
      (node (ref "D7") (pin "1") (pinfunction "CATHODE_1") (pintype "bidirectional"))
      (node (ref "R_CAPACITOR") (pin "2") (pinfunction "2_2") (pintype "passive"))
    )
    (net (code "25") (name "Net-(EPD_C1-Pad1)") (class "Default")
      (node (ref "EPD_C1") (pin "1") (pinfunction "1_1") (pintype "passive"))
      (node (ref "J1") (pin "4") (pinfunction "4_4") (pintype "bidirectional"))
    )
    (net (code "26") (name "Net-(EPD_C2-Pad1)") (class "Default")
      (node (ref "EPD_C2") (pin "1") (pinfunction "1_1") (pintype "passive"))
      (node (ref "J1") (pin "5") (pinfunction "5_5") (pintype "bidirectional"))
    )
    (net (code "27") (name "Net-(EPD_C6-Pad1)") (class "Default")
      (node (ref "EPD_C6") (pin "1") (pinfunction "1_1") (pintype "passive"))
      (node (ref "J1") (pin "18") (pinfunction "18_18") (pintype "bidirectional"))
    )
    (net (code "28") (name "Net-(EPD_C7-Pad1)") (class "Default")
      (node (ref "EPD_C7") (pin "1") (pinfunction "1_1") (pintype "passive"))
      (node (ref "J1") (pin "19") (pinfunction "19_19") (pintype "bidirectional"))
    )
    (net (code "29") (name "Net-(EPD_C8-Pad1)") (class "Default")
      (node (ref "EPD_C8") (pin "1") (pinfunction "1_1") (pintype "passive"))
      (node (ref "J1") (pin "20") (pinfunction "20_20") (pintype "bidirectional"))
    )
    (net (code "30") (name "Net-(EPD_C10-Pad1)") (class "Default")
      (node (ref "EPD_C10") (pin "1") (pinfunction "1_1") (pintype "passive"))
      (node (ref "J1") (pin "22") (pinfunction "22_22") (pintype "bidirectional"))
    )
    (net (code "31") (name "Net-(EPD_C12-Pad1)") (class "Default")
      (node (ref "EPD_C12") (pin "1") (pinfunction "1_1") (pintype "passive"))
      (node (ref "J1") (pin "24") (pinfunction "24_24") (pintype "bidirectional"))
    )
    (net (code "32") (name "Net-(IC1-CT)") (class "Default")
      (node (ref "C_DELAY") (pin "1") (pinfunction "1_1") (pintype "passive"))
      (node (ref "IC1") (pin "5") (pinfunction "CT_5") (pintype "bidirectional"))
    )
    (net (code "33") (name "Net-(J2-PadA5)") (class "Default")
      (node (ref "J2") (pin "A5") (pinfunction "A5_A5") (pintype "bidirectional"))
      (node (ref "R2-USB1") (pin "2") (pinfunction "2_2") (pintype "passive"))
    )
    (net (code "34") (name "Net-(J2-PadB5)") (class "Default")
      (node (ref "J2") (pin "B5") (pinfunction "B5_B5") (pintype "bidirectional"))
      (node (ref "R2-USB") (pin "1") (pinfunction "1_1") (pintype "passive"))
    )
    (net (code "35") (name "Net-(MCP73831-PROG)") (class "Default")
      (node (ref "MCP73831") (pin "5") (pinfunction "PROG_5") (pintype "input"))
      (node (ref "R2_BAT") (pin "2") (pinfunction "2_2") (pintype "passive"))
    )
    (net (code "36") (name "Net-(MCP73831-STAT)") (class "Default")
      (node (ref "MCP73831") (pin "1") (pinfunction "STAT_1") (pintype "output"))
      (node (ref "R1_BAT") (pin "1") (pinfunction "1_1") (pintype "passive"))
    )
    (net (code "37") (name "PREVGH") (class "Default")
      (node (ref "D5") (pin "1") (pinfunction "K_1") (pintype "bidirectional"))
      (node (ref "EPD_C9") (pin "1") (pinfunction "1_1") (pintype "passive"))
      (node (ref "J1") (pin "21") (pinfunction "21_21") (pintype "bidirectional"))
    )
    (net (code "38") (name "PREVGL") (class "Default")
      (node (ref "D4") (pin "2") (pinfunction "A_2") (pintype "bidirectional"))
      (node (ref "EPD_C11") (pin "1") (pinfunction "1_1") (pintype "passive"))
      (node (ref "J1") (pin "23") (pinfunction "23_23") (pintype "bidirectional"))
    )
    (net (code "39") (name "RESE") (class "Default")
      (node (ref "J1") (pin "3") (pinfunction "3_3") (pintype "bidirectional"))
      (node (ref "Q3") (pin "2") (pinfunction "S_2") (pintype "bidirectional"))
      (node (ref "R3") (pin "1") (pinfunction "1_1") (pintype "passive"))
    )
    (net (code "40") (name "RESE'") (class "Default")
      (node (ref "R2") (pin "2") (pinfunction "2_2") (pintype "passive"))
      (node (ref "R3") (pin "2") (pinfunction "2_2") (pintype "passive"))
      (node (ref "SJ1") (pin "2") (pinfunction "2_2") (pintype "passive"))
    )
    (net (code "41") (name "RESET") (class "Default")
      (node (ref "C5") (pin "1") (pinfunction "1_1") (pintype "passive"))
      (node (ref "IC1") (pin "1") (pinfunction "VOUT_1") (pintype "bidirectional"))
      (node (ref "RESET_BUTTON") (pin "3") (pinfunction "3_3") (pintype "passive"))
      (node (ref "RESET_BUTTON") (pin "4") (pinfunction "4_4") (pintype "passive"))
      (node (ref "R_RESET") (pin "2") (pinfunction "2_2") (pintype "passive"))
      (node (ref "U2") (pin "3") (pinfunction "EN_3") (pintype "input"))
    )
    (net (code "42") (name "RTC_RST") (class "Default")
      (node (ref "U2") (pin "16") (pinfunction "IO18_16") (pintype "bidirectional"))
      (node (ref "U3") (pin "4") (pinfunction "~{RST}_4") (pintype "input"))
    )
    (net (code "43") (name "RX") (class "Default")
      (node (ref "TP2") (pin "TP") (pinfunction "TP_TP") (pintype "input"))
      (node (ref "U2") (pin "24") (pinfunction "RXD0/GPIO17_24") (pintype "bidirectional"))
    )
    (net (code "44") (name "SCK") (class "Default")
      (node (ref "D10") (pin "1") (pinfunction "1_1") (pintype "passive"))
      (node (ref "J1") (pin "13") (pinfunction "13_13") (pintype "bidirectional"))
      (node (ref "J4") (pin "P5") (pinfunction "CLK_P5") (pintype "bidirectional"))
      (node (ref "R6") (pin "1") (pinfunction "1_1") (pintype "passive"))
      (node (ref "TP8") (pin "TP") (pinfunction "TP_TP") (pintype "input"))
      (node (ref "U1") (pin "6") (pinfunction "CLK_6") (pintype "input"))
      (node (ref "U2") (pin "6") (pinfunction "IO6_6") (pintype "bidirectional"))
    )
    (net (code "45") (name "SCL") (class "Default")
      (node (ref "J3") (pin "4") (pinfunction "4_4") (pintype "passive"))
      (node (ref "R2-PINH") (pin "1") (pinfunction "1_1") (pintype "passive"))
      (node (ref "SENSOR2") (pin "4") (pinfunction "SCK_4") (pintype "input"))
      (node (ref "U2") (pin "20") (pinfunction "IO22_20") (pintype "bidirectional"))
      (node (ref "U3") (pin "16") (pinfunction "SCL_16") (pintype "input"))
      (node (ref "U4") (pin "7") (pinfunction "SCL_7") (pintype "input"))
    )
    (net (code "46") (name "SDA") (class "Default")
      (node (ref "J3") (pin "3") (pinfunction "3_3") (pintype "passive"))
      (node (ref "R1_PINH") (pin "1") (pinfunction "1_1") (pintype "passive"))
      (node (ref "SENSOR2") (pin "3") (pinfunction "SDI_3") (pintype "bidirectional"))
      (node (ref "U2") (pin "19") (pinfunction "IO21_19") (pintype "bidirectional"))
      (node (ref "U3") (pin "15") (pinfunction "SDA_15") (pintype "bidirectional"))
      (node (ref "U4") (pin "8") (pinfunction "SDA_8") (pintype "bidirectional"))
    )
    (net (code "47") (name "SRC") (class "Default")
      (node (ref "C4") (pin "2") (pinfunction "2_2") (pintype "passive"))
      (node (ref "D5") (pin "2") (pinfunction "A_2") (pintype "bidirectional"))
      (node (ref "L1") (pin "1") (pinfunction "1_1") (pintype "passive"))
      (node (ref "Q3") (pin "3") (pinfunction "D_3") (pintype "bidirectional"))
    )
    (net (code "48") (name "SS_SD") (class "Default")
      (node (ref "D8") (pin "1") (pinfunction "1_1") (pintype "passive"))
      (node (ref "J4") (pin "P2") (pinfunction "CD/DAT3_P2") (pintype "bidirectional"))
      (node (ref "R10") (pin "1") (pinfunction "1_1") (pintype "passive"))
      (node (ref "U2") (pin "4") (pinfunction "IO4_4") (pintype "bidirectional"))
    )
    (net (code "49") (name "TX") (class "Default")
      (node (ref "TP1") (pin "TP") (pinfunction "TP_TP") (pintype "input"))
      (node (ref "U2") (pin "25") (pinfunction "TXD0/GPIO16_25") (pintype "bidirectional"))
    )
    (net (code "50") (name "USB_D+") (class "Default")
      (node (ref "D1") (pin "1") (pinfunction "I/O1_1_1") (pintype "bidirectional"))
      (node (ref "U2") (pin "14") (pinfunction "IO13_14") (pintype "bidirectional"))
    )
    (net (code "51") (name "USB_D-") (class "Default")
      (node (ref "D1") (pin "3") (pinfunction "I/O2_1_3") (pintype "bidirectional"))
      (node (ref "U2") (pin "13") (pinfunction "IO12_13") (pintype "bidirectional"))
    )
    (net (code "52") (name "VBAT") (class "Default")
      (node (ref "C2_BAT") (pin "1") (pinfunction "1_1") (pintype "passive"))
      (node (ref "MCP73831") (pin "3") (pinfunction "VBAT_3") (pintype "power_in"))
      (node (ref "Q1") (pin "3") (pinfunction "D_3") (pintype "bidirectional"))
      (node (ref "TP3") (pin "TP") (pinfunction "TP_TP") (pintype "input"))
      (node (ref "U4") (pin "2") (pinfunction "CELL_2") (pintype "power_in"))
      (node (ref "U4") (pin "3") (pinfunction "VDD_3") (pintype "power_in"))
    )
    (net (code "53") (name "VBUS") (class "Default")
      (node (ref "C1_BAT") (pin "1") (pinfunction "1_1") (pintype "passive"))
      (node (ref "C4_USB") (pin "1") (pinfunction "1_1") (pintype "passive"))
      (node (ref "C5_USB") (pin "1") (pinfunction "1_1") (pintype "passive"))
      (node (ref "CHG_LED") (pin "A") (pinfunction "A_A") (pintype "passive"))
      (node (ref "D1") (pin "5") (pinfunction "VBUS_5") (pintype "bidirectional"))
      (node (ref "D2") (pin "2") (pinfunction "ANODE_2") (pintype "bidirectional"))
      (node (ref "MCP73831") (pin "4") (pinfunction "VIN_4") (pintype "power_in"))
      (node (ref "PFMF.050.1") (pin "2") (pinfunction "2_2") (pintype "passive"))
      (node (ref "Q1") (pin "1") (pinfunction "G_1") (pintype "bidirectional"))
      (node (ref "R1_PWRUSB") (pin "2") (pinfunction "2_2") (pintype "passive"))
      (node (ref "TP14") (pin "TP") (pinfunction "TP_TP") (pintype "input"))
    )
    (net (code "54") (name "VRTC") (class "Default")
      (node (ref "C10_SUPERCAP") (pin "2") (pinfunction "2_2") (pintype "passive"))
      (node (ref "C8") (pin "1") (pinfunction "1_1") (pintype "passive"))
      (node (ref "R_CAPACITOR") (pin "1") (pinfunction "1_1") (pintype "passive"))
      (node (ref "U3") (pin "14") (pinfunction "VBAT_14") (pintype "power_in"))
    )
    (net (code "55") (name "VUSB") (class "Default")
      (node (ref "J2") (pin "A4") (pinfunction "A4_A4") (pintype "bidirectional"))
      (node (ref "J2") (pin "A9") (pinfunction "A9_A9") (pintype "bidirectional"))
      (node (ref "J2") (pin "B4") (pinfunction "B4_B4") (pintype "bidirectional"))
      (node (ref "J2") (pin "B9") (pinfunction "B9_B9") (pintype "bidirectional"))
      (node (ref "PFMF.050.1") (pin "1") (pinfunction "1_1") (pintype "passive"))
    )
    (net (code "56") (name "unconnected-(IC1-NC-Pad4)") (class "Default")
      (node (ref "IC1") (pin "4") (pinfunction "NC_4") (pintype "no_connect"))
    )
    (net (code "57") (name "unconnected-(IC4-NC-Pad4)") (class "Default")
      (node (ref "IC4") (pin "4") (pinfunction "NC_4") (pintype "no_connect"))
    )
    (net (code "58") (name "unconnected-(J1-Pad1)") (class "Default")
      (node (ref "J1") (pin "1") (pinfunction "1_1") (pintype "bidirectional"))
    )
    (net (code "59") (name "unconnected-(J1-Pad6)") (class "Default")
      (node (ref "J1") (pin "6") (pinfunction "6_6") (pintype "bidirectional"))
    )
    (net (code "60") (name "unconnected-(J1-Pad7)") (class "Default")
      (node (ref "J1") (pin "7") (pinfunction "7_7") (pintype "bidirectional"))
    )
    (net (code "61") (name "unconnected-(J2-PadA8)") (class "Default")
      (node (ref "J2") (pin "A8") (pinfunction "A8_A8") (pintype "bidirectional"))
    )
    (net (code "62") (name "unconnected-(J2-PadB8)") (class "Default")
      (node (ref "J2") (pin "B8") (pinfunction "B8_B8") (pintype "bidirectional"))
    )
    (net (code "63") (name "unconnected-(J4-DAT1-PadP8)") (class "Default")
      (node (ref "J4") (pin "P8") (pinfunction "DAT1_P8") (pintype "bidirectional"))
    )
    (net (code "64") (name "unconnected-(J4-DAT2-PadP1)") (class "Default")
      (node (ref "J4") (pin "P1") (pinfunction "DAT2_P1") (pintype "bidirectional"))
    )
    (net (code "65") (name "unconnected-(J4-DETECTION_1-PadS1)") (class "Default")
      (node (ref "J4") (pin "S1") (pinfunction "DETECTION_1_S1") (pintype "bidirectional"))
    )
    (net (code "66") (name "unconnected-(J4-DETECTION_2-PadS2)") (class "Default")
      (node (ref "J4") (pin "S2") (pinfunction "DETECTION_2_S2") (pintype "bidirectional"))
    )
    (net (code "67") (name "unconnected-(U2-NC-Pad22)") (class "Default")
      (node (ref "U2") (pin "22") (pinfunction "NC_22") (pintype "no_connect"))
    )
    (net (code "68") (name "unconnected-(U4-~{ALERT}-Pad5)") (class "Default")
      (node (ref "U4") (pin "5") (pinfunction "~{ALERT}_5") (pintype "output"))
    )
  )
)
